# XSB.net
KiCad netlist of a schematic drawn in Altium Designer
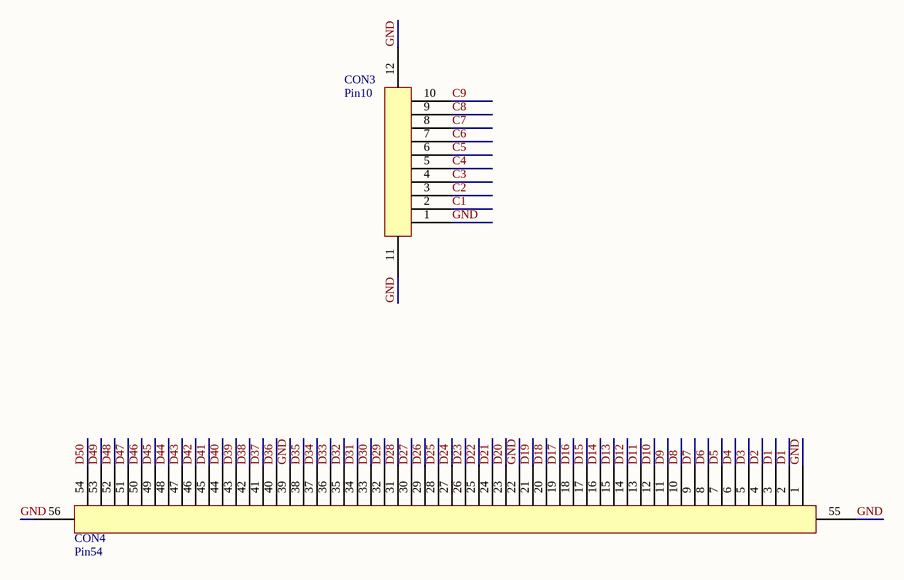
[diagram p0: XSB.SchDoc]

(export (version "E")
  (design (tool "Eeschema 10.0.6"))
  (components
    (comp (ref "CON3") (value "Pin10") (footprint "Pin10") (libsource (lib "IPHONEX") (part "Pin10")))
    (comp (ref "CON4") (value "Pin54") (footprint "Pin54") (libsource (lib "IPHONEX") (part "Pin54")))
  )
  (nets
    (net (code "1") (name "/C1") (class "Default") (node (ref "CON3") (pin "2") (pintype "passive")))
    (net (code "2") (name "/C2") (class "Default") (node (ref "CON3") (pin "3") (pintype "passive")))
    (net (code "3") (name "/C3") (class "Default") (node (ref "CON3") (pin "4") (pintype "passive")))
    (net (code "4") (name "/C4") (class "Default") (node (ref "CON3") (pin "5") (pintype "passive")))
    (net (code "5") (name "/C5") (class "Default") (node (ref "CON3") (pin "6") (pintype "passive")))
    (net (code "6") (name "/C6") (class "Default") (node (ref "CON3") (pin "7") (pintype "passive")))
    (net (code "7") (name "/C7") (class "Default") (node (ref "CON3") (pin "8") (pintype "passive")))
    (net (code "8") (name "/C8") (class "Default") (node (ref "CON3") (pin "9") (pintype "passive")))
    (net (code "9") (name "/C9") (class "Default") (node (ref "CON3") (pin "10") (pintype "passive")))
    (net (code "10") (name "/D1") (class "Default")
      (node (ref "CON4") (pin "2") (pintype "passive"))
      (node (ref "CON4") (pin "3") (pintype "passive"))
    )
    (net (code "11") (name "/D2") (class "Default") (node (ref "CON4") (pin "4") (pintype "passive")))
    (net (code "12") (name "/D3") (class "Default") (node (ref "CON4") (pin "5") (pintype "passive")))
    (net (code "13") (name "/D4") (class "Default") (node (ref "CON4") (pin "6") (pintype "passive")))
    (net (code "14") (name "/D5") (class "Default") (node (ref "CON4") (pin "7") (pintype "passive")))
    (net (code "15") (name "/D6") (class "Default") (node (ref "CON4") (pin "8") (pintype "passive")))
    (net (code "16") (name "/D7") (class "Default") (node (ref "CON4") (pin "9") (pintype "passive")))
    (net (code "17") (name "/D8") (class "Default") (node (ref "CON4") (pin "10") (pintype "passive")))
    (net (code "18") (name "/D9") (class "Default") (node (ref "CON4") (pin "11") (pintype "passive")))
    (net (code "19") (name "/D10") (class "Default") (node (ref "CON4") (pin "12") (pintype "passive")))
    (net (code "20") (name "/D11") (class "Default") (node (ref "CON4") (pin "13") (pintype "passive")))
    (net (code "21") (name "/D12") (class "Default") (node (ref "CON4") (pin "14") (pintype "passive")))
    (net (code "22") (name "/D13") (class "Default") (node (ref "CON4") (pin "15") (pintype "passive")))
    (net (code "23") (name "/D14") (class "Default") (node (ref "CON4") (pin "16") (pintype "passive")))
    (net (code "24") (name "/D15") (class "Default") (node (ref "CON4") (pin "17") (pintype "passive")))
    (net (code "25") (name "/D16") (class "Default") (node (ref "CON4") (pin "18") (pintype "passive")))
    (net (code "26") (name "/D17") (class "Default") (node (ref "CON4") (pin "19") (pintype "passive")))
    (net (code "27") (name "/D18") (class "Default") (node (ref "CON4") (pin "20") (pintype "passive")))
    (net (code "28") (name "/D19") (class "Default") (node (ref "CON4") (pin "21") (pintype "passive")))
    (net (code "29") (name "/D20") (class "Default") (node (ref "CON4") (pin "23") (pintype "passive")))
    (net (code "30") (name "/D21") (class "Default") (node (ref "CON4") (pin "24") (pintype "passive")))
    (net (code "31") (name "/D22") (class "Default") (node (ref "CON4") (pin "25") (pintype "passive")))
    (net (code "32") (name "/D23") (class "Default") (node (ref "CON4") (pin "26") (pintype "passive")))
    (net (code "33") (name "/D24") (class "Default") (node (ref "CON4") (pin "27") (pintype "passive")))
    (net (code "34") (name "/D25") (class "Default") (node (ref "CON4") (pin "28") (pintype "passive")))
    (net (code "35") (name "/D26") (class "Default") (node (ref "CON4") (pin "29") (pintype "passive")))
    (net (code "36") (name "/D27") (class "Default") (node (ref "CON4") (pin "30") (pintype "passive")))
    (net (code "37") (name "/D28") (class "Default") (node (ref "CON4") (pin "31") (pintype "passive")))
    (net (code "38") (name "/D29") (class "Default") (node (ref "CON4") (pin "32") (pintype "passive")))
    (net (code "39") (name "/D30") (class "Default") (node (ref "CON4") (pin "33") (pintype "passive")))
    (net (code "40") (name "/D31") (class "Default") (node (ref "CON4") (pin "34") (pintype "passive")))
    (net (code "41") (name "/D32") (class "Default") (node (ref "CON4") (pin "35") (pintype "passive")))
    (net (code "42") (name "/D33") (class "Default") (node (ref "CON4") (pin "36") (pintype "passive")))
    (net (code "43") (name "/D34") (class "Default") (node (ref "CON4") (pin "37") (pintype "passive")))
    (net (code "44") (name "/D35") (class "Default") (node (ref "CON4") (pin "38") (pintype "passive")))
    (net (code "45") (name "/D36") (class "Default") (node (ref "CON4") (pin "40") (pintype "passive")))
    (net (code "46") (name "/D37") (class "Default") (node (ref "CON4") (pin "41") (pintype "passive")))
    (net (code "47") (name "/D38") (class "Default") (node (ref "CON4") (pin "42") (pintype "passive")))
    (net (code "48") (name "/D39") (class "Default") (node (ref "CON4") (pin "43") (pintype "passive")))
    (net (code "49") (name "/D40") (class "Default") (node (ref "CON4") (pin "44") (pintype "passive")))
    (net (code "50") (name "/D41") (class "Default") (node (ref "CON4") (pin "45") (pintype "passive")))
    (net (code "51") (name "/D42") (class "Default") (node (ref "CON4") (pin "46") (pintype "passive")))
    (net (code "52") (name "/D43") (class "Default") (node (ref "CON4") (pin "47") (pintype "passive")))
    (net (code "53") (name "/D44") (class "Default") (node (ref "CON4") (pin "48") (pintype "passive")))
    (net (code "54") (name "/D45") (class "Default") (node (ref "CON4") (pin "49") (pintype "passive")))
    (net (code "55") (name "/D46") (class "Default") (node (ref "CON4") (pin "50") (pintype "passive")))
    (net (code "56") (name "/D47") (class "Default") (node (ref "CON4") (pin "51") (pintype "passive")))
    (net (code "57") (name "/D48") (class "Default") (node (ref "CON4") (pin "52") (pintype "passive")))
    (net (code "58") (name "/D49") (class "Default") (node (ref "CON4") (pin "53") (pintype "passive")))
    (net (code "59") (name "/D50") (class "Default") (node (ref "CON4") (pin "54") (pintype "passive")))
    (net (code "60") (name "/GND") (class "Default")
      (node (ref "CON3") (pin "1") (pintype "passive"))
      (node (ref "CON3") (pin "11") (pintype "passive"))
      (node (ref "CON3") (pin "12") (pintype "passive"))
      (node (ref "CON4") (pin "1") (pintype "passive"))
      (node (ref "CON4") (pin "22") (pintype "passive"))
      (node (ref "CON4") (pin "39") (pintype "passive"))
      (node (ref "CON4") (pin "55") (pintype "passive"))
      (node (ref "CON4") (pin "56") (pintype "passive"))
    )
  )
)
